# B_Sensor_Board_Digital_v1_1.net
KiCad netlist of a schematic drawn in EAGLE
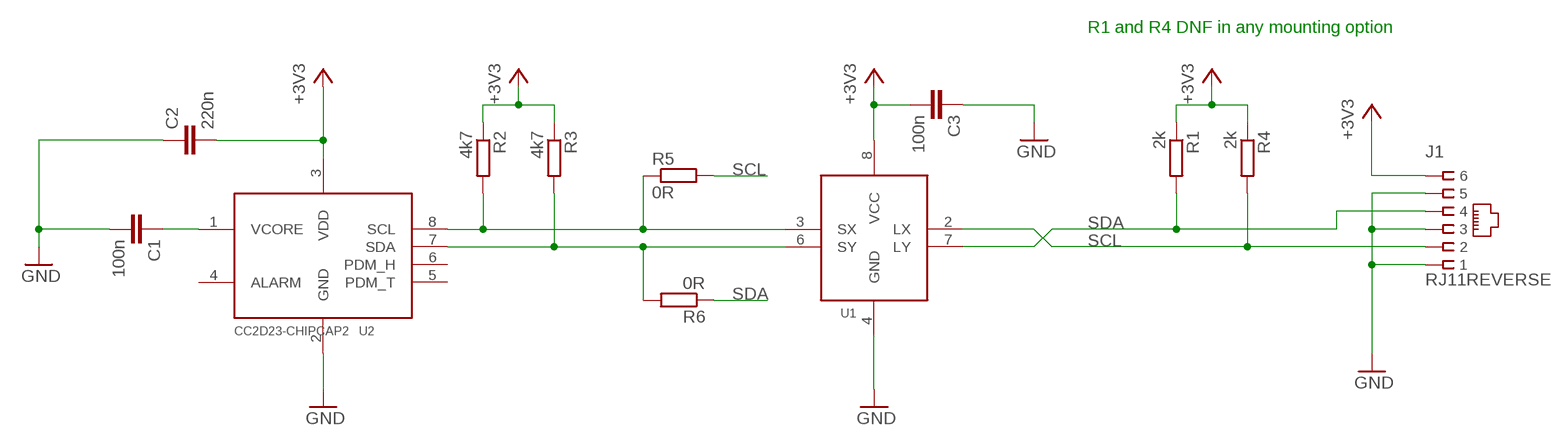
[diagram p0: schematic, sheet 1]

(export (version "E")
  (design (tool "Eeschema 10.0.6"))
  (components
    (comp (ref "C1")
      (value "100n")
      (footprint "eagle-import:C1206")
      (libsource (lib "eagle-import") (part "C-EUC1206"))
    )
    (comp (ref "C2")
      (value "220n")
      (footprint "eagle-import:C1206")
      (libsource (lib "eagle-import") (part "C-EUC1206"))
    )
    (comp (ref "C3")
      (value "100n")
      (footprint "eagle-import:C1206")
      (libsource (lib "eagle-import") (part "C-EUC1206"))
    )
    (comp (ref "J1")
      (value "RJ11REVERSE")
      (footprint "eagle-import:MX-95001-2661")
      (libsource (lib "eagle-import") (part "RJ11REVERSE"))
    )
    (comp (ref "R1")
      (value "2k")
      (footprint "eagle-import:R1206")
      (libsource (lib "eagle-import") (part "R-EU_R1206"))
    )
    (comp (ref "R2")
      (value "4k7")
      (footprint "eagle-import:R1206")
      (libsource (lib "eagle-import") (part "R-EU_R1206"))
    )
    (comp (ref "R3")
      (value "4k7")
      (footprint "eagle-import:R1206")
      (libsource (lib "eagle-import") (part "R-EU_R1206"))
    )
    (comp (ref "R4")
      (value "2k")
      (footprint "eagle-import:R1206")
      (libsource (lib "eagle-import") (part "R-EU_R1206"))
    )
    (comp (ref "R5")
      (value "0R")
      (footprint "eagle-import:R1206")
      (libsource (lib "eagle-import") (part "R-EU_R1206"))
    )
    (comp (ref "R6")
      (value "0R")
      (footprint "eagle-import:R1206")
      (libsource (lib "eagle-import") (part "R-EU_R1206"))
    )
    (comp (ref "U1")
      (value "P82B715_I2C_BUS_EXTENDER")
      (footprint "eagle-import:SO-08")
      (libsource (lib "eagle-import") (part "P82B715_I2C_BUS_EXTENDER"))
    )
    (comp (ref "U2")
      (value "CC2D23-CHIPCAP2")
      (footprint "eagle-import:CC2D23-CHIPCAP2")
      (libsource (lib "eagle-import") (part "CC2D23-CHIPCAP2"))
    )
  )
  (nets
    (net (code "1") (name "+3V3") (class "Default")
      (node (ref "C2") (pin "2") (pinfunction "2_2") (pintype "passive"))
      (node (ref "C3") (pin "2") (pinfunction "2_2") (pintype "passive"))
      (node (ref "J1") (pin "6") (pinfunction "6_6") (pintype "passive"))
      (node (ref "R1") (pin "1") (pinfunction "1_1") (pintype "passive"))
      (node (ref "R2") (pin "1") (pinfunction "1_1") (pintype "passive"))
      (node (ref "R3") (pin "1") (pinfunction "1_1") (pintype "passive"))
      (node (ref "R4") (pin "1") (pinfunction "1_1") (pintype "passive"))
      (node (ref "U1") (pin "8") (pinfunction "VCC_8") (pintype "bidirectional"))
      (node (ref "U2") (pin "3") (pinfunction "VDD_3") (pintype "bidirectional"))
    )
    (net (code "2") (name "/SCL") (class "Default")
      (node (ref "J1") (pin "2") (pinfunction "2_2") (pintype "passive"))
      (node (ref "R4") (pin "2") (pinfunction "2_2") (pintype "passive"))
      (node (ref "R5") (pin "2") (pinfunction "2_2") (pintype "passive"))
      (node (ref "U1") (pin "2") (pinfunction "LX_2") (pintype "bidirectional"))
    )
    (net (code "3") (name "/SDA") (class "Default")
      (node (ref "J1") (pin "4") (pinfunction "4_4") (pintype "passive"))
      (node (ref "R1") (pin "2") (pinfunction "2_2") (pintype "passive"))
      (node (ref "R6") (pin "1") (pinfunction "1_1") (pintype "passive"))
      (node (ref "U1") (pin "7") (pinfunction "LY_7") (pintype "bidirectional"))
    )
    (net (code "4") (name "GND") (class "Default")
      (node (ref "C1") (pin "2") (pinfunction "2_2") (pintype "passive"))
      (node (ref "C2") (pin "1") (pinfunction "1_1") (pintype "passive"))
      (node (ref "C3") (pin "1") (pinfunction "1_1") (pintype "passive"))
      (node (ref "J1") (pin "1") (pinfunction "1_1") (pintype "passive"))
      (node (ref "J1") (pin "3") (pinfunction "3_3") (pintype "passive"))
      (node (ref "J1") (pin "5") (pinfunction "5_5") (pintype "passive"))
      (node (ref "U1") (pin "4") (pinfunction "GND_4") (pintype "bidirectional"))
      (node (ref "U2") (pin "2") (pinfunction "GND_2") (pintype "bidirectional"))
    )
    (net (code "5") (name "Net-(U1-SX)") (class "Default")
      (node (ref "R2") (pin "2") (pinfunction "2_2") (pintype "passive"))
      (node (ref "R5") (pin "1") (pinfunction "1_1") (pintype "passive"))
      (node (ref "U1") (pin "3") (pinfunction "SX_3") (pintype "bidirectional"))
      (node (ref "U2") (pin "8") (pinfunction "SCL_8") (pintype "bidirectional"))
    )
    (net (code "6") (name "Net-(U1-SY)") (class "Default")
      (node (ref "R3") (pin "2") (pinfunction "2_2") (pintype "passive"))
      (node (ref "R6") (pin "2") (pinfunction "2_2") (pintype "passive"))
      (node (ref "U1") (pin "6") (pinfunction "SY_6") (pintype "bidirectional"))
      (node (ref "U2") (pin "7") (pinfunction "SDA_7") (pintype "bidirectional"))
    )
    (net (code "7") (name "Net-(U2-VCORE)") (class "Default")
      (node (ref "C1") (pin "1") (pinfunction "1_1") (pintype "passive"))
      (node (ref "U2") (pin "1") (pinfunction "VCORE_1") (pintype "bidirectional"))
    )
    (net (code "8") (name "unconnected-(U2-ALARM-Pad4)") (class "Default")
      (node (ref "U2") (pin "4") (pinfunction "ALARM_4") (pintype "bidirectional"))
    )
    (net (code "9") (name "unconnected-(U2-PDM_H-Pad6)") (class "Default")
      (node (ref "U2") (pin "6") (pinfunction "PDM_H_6") (pintype "bidirectional"))
    )
    (net (code "10") (name "unconnected-(U2-PDM_T-Pad5)") (class "Default")
      (node (ref "U2") (pin "5") (pinfunction "PDM_T_5") (pintype "bidirectional"))
    )
  )
)
